# Sheet1.net
KiCad netlist of a schematic drawn in Altium Designer
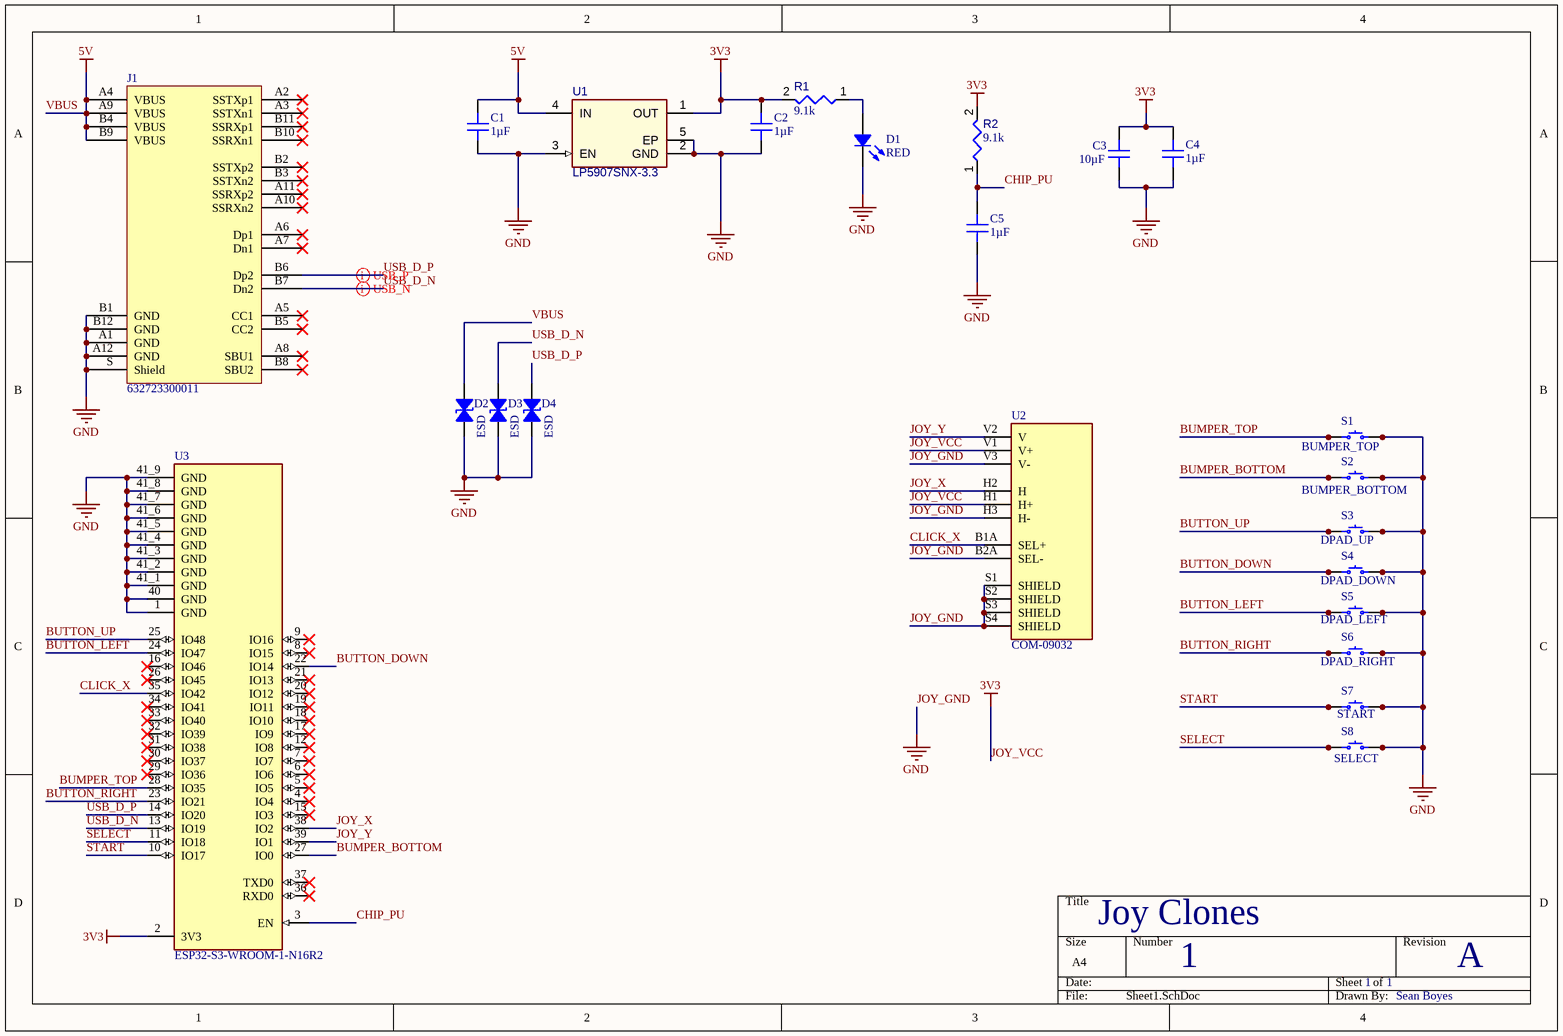
[diagram p0: Sheet1.SchDoc]

(export (version "E")
  (design (tool "Eeschema 10.0.6"))
  (components
    (comp (ref "C1")
      (value "1µF")
      (footprint "CAP 0402_1005")
      (description "CAP CER 1UF 10V X7S 0402")
      (fields (field (name "PART NUMBER") "CL05Y105KP6VPNC") (field (name "TOLERANCE") "10%"))
      (libsource (lib "Simon Fraser University") (part "CAPACITOR"))
    )
    (comp (ref "C2")
      (value "1µF")
      (footprint "CAP 0402_1005")
      (description "CAP CER 1UF 10V X7S 0402")
      (fields (field (name "PART NUMBER") "CL05Y105KP6VPNC") (field (name "TOLERANCE") "10%"))
      (libsource (lib "Simon Fraser University") (part "CAPACITOR"))
    )
    (comp (ref "C3")
      (value "10µF")
      (footprint "CAP 0603_1608")
      (description "CAP CER 10UF 6.3V X6S 0603")
      (fields (field (name "TOLERANCE") "20%") (field (name "PART NUMBER") "GRM188C80J106MEA6J"))
      (libsource (lib "Simon Fraser University") (part "CAPACITOR"))
    )
    (comp (ref "C4")
      (value "1µF")
      (footprint "CAP 0402_1005")
      (description "CAP CER 1UF 10V X7S 0402")
      (fields (field (name "PART NUMBER") "CL05Y105KP6VPNC") (field (name "TOLERANCE") "10%"))
      (libsource (lib "Simon Fraser University") (part "CAPACITOR"))
    )
    (comp (ref "C5")
      (value "1µF")
      (footprint "CAP 0402_1005")
      (description "CAP CER 1UF 10V X7S 0402")
      (fields (field (name "PART NUMBER") "CL05Y105KP6VPNC") (field (name "TOLERANCE") "10%"))
      (libsource (lib "Simon Fraser University") (part "CAPACITOR"))
    )
    (comp (ref "D1")
      (value "RED")
      (footprint "LED 0603_1608 RED")
      (description "LED RED CLEAR 2SMD")
      (fields
        (field (name "MANUFACTURER") "Everlight Electronics Co Ltd")
        (field (name "PART NUMBER") "EAST16084RA0")
      )
      (libsource (lib "Simon Fraser University") (part "LED"))
    )
    (comp (ref "D2")
      (value "ESD")
      (footprint "0402")
      (description "TVS DIODE 5V 8.2V 2X2DFN")
      (fields (field (name "PART NUMBER") "ESDM3051N2T5G") (field (name "MANUFACTURER") "ON Semiconductor"))
      (libsource (lib "Simon Fraser University") (part "DIODE TVS"))
    )
    (comp (ref "D3")
      (value "ESD")
      (footprint "0402")
      (description "TVS DIODE 5V 8.2V 2X2DFN")
      (fields (field (name "PART NUMBER") "ESDM3051N2T5G") (field (name "MANUFACTURER") "ON Semiconductor"))
      (libsource (lib "Simon Fraser University") (part "DIODE TVS"))
    )
    (comp (ref "D4")
      (value "ESD")
      (footprint "0402")
      (description "TVS DIODE 5V 8.2V 2X2DFN")
      (fields (field (name "PART NUMBER") "ESDM3051N2T5G") (field (name "MANUFACTURER") "ON Semiconductor"))
      (libsource (lib "Simon Fraser University") (part "DIODE TVS"))
    )
    (comp (ref "J1")
      (value "632723300011")
      (footprint "WURTH 632723300011")
      (description "CONN RCP USB3.1 TYPEC 24P SMD RA")
      (fields (field (name "MANUFACTURER") "Würth Elektronik"))
      (libsource (lib "Simon Fraser University") (part "USB 3.0 TYPE C"))
    )
    (comp (ref "R1")
      (value "9.1k")
      (footprint "RESC0402(1005)_L")
      (description "9K1 0.063W 5% 0402 (1005 Metric)  SMD")
      (fields (field (name "POWER") "63mW") (field (name "TOLERANCE") "5%"))
      (libsource (lib "Simon Fraser University") (part "Res"))
    )
    (comp (ref "R2")
      (value "9.1k")
      (footprint "RESC0402(1005)_L")
      (description "9K1 0.063W 5% 0402 (1005 Metric)  SMD")
      (fields (field (name "POWER") "63mW") (field (name "TOLERANCE") "5%"))
      (libsource (lib "Simon Fraser University") (part "Res"))
    )
    (comp (ref "S1")
      (value "BUMPER_TOP")
      (footprint "C&K PTS810")
      (description "SWITCH TACTILE SPST-NO 0.05A 16V")
      (fields (field (name "PART NUMBER") "PTS810 SJM 250 SMTR LFS") (field (name "MANUFACTURER") "C&K"))
      (libsource (lib "Simon Fraser University") (part "SPST-NO 4 PIN"))
    )
    (comp (ref "S2")
      (value "BUMPER_BOTTOM")
      (footprint "C&K PTS810")
      (description "SWITCH TACTILE SPST-NO 0.05A 16V")
      (fields (field (name "PART NUMBER") "PTS810 SJM 250 SMTR LFS") (field (name "MANUFACTURER") "C&K"))
      (libsource (lib "Simon Fraser University") (part "SPST-NO 4 PIN"))
    )
    (comp (ref "S3")
      (value "DPAD_UP")
      (footprint "C&K PTS810")
      (description "SWITCH TACTILE SPST-NO 0.05A 16V")
      (fields (field (name "PART NUMBER") "PTS810 SJM 250 SMTR LFS") (field (name "MANUFACTURER") "C&K"))
      (libsource (lib "Simon Fraser University") (part "SPST-NO 4 PIN"))
    )
    (comp (ref "S4")
      (value "DPAD_DOWN")
      (footprint "C&K PTS810")
      (description "SWITCH TACTILE SPST-NO 0.05A 16V")
      (fields (field (name "PART NUMBER") "PTS810 SJM 250 SMTR LFS") (field (name "MANUFACTURER") "C&K"))
      (libsource (lib "Simon Fraser University") (part "SPST-NO 4 PIN"))
    )
    (comp (ref "S5")
      (value "DPAD_LEFT")
      (footprint "C&K PTS810")
      (description "SWITCH TACTILE SPST-NO 0.05A 16V")
      (fields (field (name "PART NUMBER") "PTS810 SJM 250 SMTR LFS") (field (name "MANUFACTURER") "C&K"))
      (libsource (lib "Simon Fraser University") (part "SPST-NO 4 PIN"))
    )
    (comp (ref "S6")
      (value "DPAD_RIGHT")
      (footprint "C&K PTS810")
      (description "SWITCH TACTILE SPST-NO 0.05A 16V")
      (fields (field (name "PART NUMBER") "PTS810 SJM 250 SMTR LFS") (field (name "MANUFACTURER") "C&K"))
      (libsource (lib "Simon Fraser University") (part "SPST-NO 4 PIN"))
    )
    (comp (ref "S7")
      (value "START")
      (footprint "C&K PTS810")
      (description "SWITCH TACTILE SPST-NO 0.05A 16V")
      (fields (field (name "PART NUMBER") "PTS810 SJM 250 SMTR LFS") (field (name "MANUFACTURER") "C&K"))
      (libsource (lib "Simon Fraser University") (part "SPST-NO 4 PIN"))
    )
    (comp (ref "S8")
      (value "SELECT")
      (footprint "C&K PTS810")
      (description "SWITCH TACTILE SPST-NO 0.05A 16V")
      (fields (field (name "PART NUMBER") "PTS810 SJM 250 SMTR LFS") (field (name "MANUFACTURER") "C&K"))
      (libsource (lib "Simon Fraser University") (part "SPST-NO 4 PIN"))
    )
    (comp (ref "U1")
      (value "LP5907SNX-3.3")
      (footprint "TI-DQN4-480X480TP_V")
      (description "Ultra-Low-Noise, Low-IQ LDO, 3.3 V, 0.25 A, -40 to 125 degC, 4-Pin X2SON, RoHS, Tape and Reel")
      (libsource (lib "Simon Fraser University") (part "CMP-00094-7"))
    )
    (comp (ref "U2")
      (value "COM-09032")
      (footprint "XDCR_COM-09032")
      (description "Thumb Joystick")
      (libsource (lib "COM-09032") (part "COM-09032"))
    )
    (comp (ref "U3")
      (value "ESP32-S3-WROOM-1-N16R2")
      (footprint "XCVR_ESP32-S3-WROOM-1-N16R2")
      (description "Bluetooth, WiFi 802.11b/g/n, Bluetooth v5.0 Transceiver Module 2.4GHz PCB Trace Surface Mount")
      (fields (field (name "MF") "Espressif Systems"))
      (libsource (lib "Simon Fraser University") (part "ESP32-S3-WROOM-1-N16R2"))
    )
  )
  (nets
    (net (code "1") (name "/BUMPER_BOTTOM") (class "Default")
      (node (ref "S2") (pin "1") (pinfunction "1_1") (pintype "passive"))
      (node (ref "S2") (pin "2") (pinfunction "2_2") (pintype "passive"))
      (node (ref "U3") (pin "27") (pinfunction "IO0_27") (pintype "bidirectional"))
    )
    (net (code "2") (name "/BUMPER_TOP") (class "Default")
      (node (ref "S1") (pin "1") (pinfunction "1_1") (pintype "passive"))
      (node (ref "S1") (pin "2") (pinfunction "2_2") (pintype "passive"))
      (node (ref "U3") (pin "28") (pinfunction "IO35_28") (pintype "bidirectional"))
    )
    (net (code "3") (name "/BUTTON_DOWN") (class "Default")
      (node (ref "S4") (pin "1") (pinfunction "1_1") (pintype "passive"))
      (node (ref "S4") (pin "2") (pinfunction "2_2") (pintype "passive"))
      (node (ref "U3") (pin "22") (pinfunction "IO14_22") (pintype "bidirectional"))
    )
    (net (code "4") (name "/BUTTON_LEFT") (class "Default")
      (node (ref "S5") (pin "1") (pinfunction "1_1") (pintype "passive"))
      (node (ref "S5") (pin "2") (pinfunction "2_2") (pintype "passive"))
      (node (ref "U3") (pin "24") (pinfunction "IO47_24") (pintype "bidirectional"))
    )
    (net (code "5") (name "/BUTTON_RIGHT") (class "Default")
      (node (ref "S6") (pin "1") (pinfunction "1_1") (pintype "passive"))
      (node (ref "S6") (pin "2") (pinfunction "2_2") (pintype "passive"))
      (node (ref "U3") (pin "23") (pinfunction "IO21_23") (pintype "bidirectional"))
    )
    (net (code "6") (name "/BUTTON_UP") (class "Default")
      (node (ref "S3") (pin "1") (pinfunction "1_1") (pintype "passive"))
      (node (ref "S3") (pin "2") (pinfunction "2_2") (pintype "passive"))
      (node (ref "U3") (pin "25") (pinfunction "IO48_25") (pintype "bidirectional"))
    )
    (net (code "7") (name "/CHIP_PU") (class "Default")
      (node (ref "C5") (pin "2") (pinfunction "2_2") (pintype "passive"))
      (node (ref "R2") (pin "1") (pinfunction "1_1") (pintype "passive"))
      (node (ref "U3") (pin "3") (pinfunction "EN_3") (pintype "input"))
    )
    (net (code "8") (name "/CLICK_X") (class "Default")
      (node (ref "U2") (pin "B1A") (pinfunction "SEL+_B1A") (pintype "passive"))
      (node (ref "U3") (pin "35") (pinfunction "IO42_35") (pintype "bidirectional"))
    )
    (net (code "9") (name "/JOY_X") (class "Default")
      (node (ref "U2") (pin "H2") (pinfunction "H_H2") (pintype "passive"))
      (node (ref "U3") (pin "38") (pinfunction "IO2_38") (pintype "bidirectional"))
    )
    (net (code "10") (name "/JOY_Y") (class "Default")
      (node (ref "U2") (pin "V2") (pinfunction "V_V2") (pintype "passive"))
      (node (ref "U3") (pin "39") (pinfunction "IO1_39") (pintype "bidirectional"))
    )
    (net (code "11") (name "/SELECT") (class "Default")
      (node (ref "S8") (pin "1") (pinfunction "1_1") (pintype "passive"))
      (node (ref "S8") (pin "2") (pinfunction "2_2") (pintype "passive"))
      (node (ref "U3") (pin "11") (pinfunction "IO18_11") (pintype "bidirectional"))
    )
    (net (code "12") (name "/START") (class "Default")
      (node (ref "S7") (pin "1") (pinfunction "1_1") (pintype "passive"))
      (node (ref "S7") (pin "2") (pinfunction "2_2") (pintype "passive"))
      (node (ref "U3") (pin "10") (pinfunction "IO17_10") (pintype "bidirectional"))
    )
    (net (code "13") (name "/USB_D_N") (class "Default")
      (node (ref "D3") (pin "1") (pinfunction "1_1") (pintype "passive"))
      (node (ref "J1") (pin "B7") (pinfunction "Dn2_B7") (pintype "passive"))
      (node (ref "U3") (pin "13") (pinfunction "IO19_13") (pintype "bidirectional"))
    )
    (net (code "14") (name "/USB_D_P") (class "Default")
      (node (ref "D4") (pin "1") (pinfunction "1_1") (pintype "passive"))
      (node (ref "J1") (pin "B6") (pinfunction "Dp2_B6") (pintype "passive"))
      (node (ref "U3") (pin "14") (pinfunction "IO20_14") (pintype "bidirectional"))
    )
    (net (code "15") (name "3V3") (class "Default")
      (node (ref "C2") (pin "2") (pinfunction "2_2") (pintype "passive"))
      (node (ref "C3") (pin "2") (pinfunction "2_2") (pintype "passive"))
      (node (ref "C4") (pin "2") (pinfunction "2_2") (pintype "passive"))
      (node (ref "R1") (pin "2") (pinfunction "2_2") (pintype "passive"))
      (node (ref "R2") (pin "2") (pinfunction "2_2") (pintype "passive"))
      (node (ref "U1") (pin "1") (pinfunction "OUT_1") (pintype "power_in"))
      (node (ref "U2") (pin "H1") (pinfunction "H+_H1") (pintype "passive"))
      (node (ref "U2") (pin "V1") (pinfunction "V+_V1") (pintype "passive"))
      (node (ref "U3") (pin "2") (pinfunction "3V3_2") (pintype "power_in"))
    )
    (net (code "16") (name "5V") (class "Default")
      (node (ref "C1") (pin "2") (pinfunction "2_2") (pintype "passive"))
      (node (ref "D2") (pin "1") (pinfunction "1_1") (pintype "passive"))
      (node (ref "J1") (pin "A4") (pinfunction "VBUS_A4") (pintype "passive"))
      (node (ref "J1") (pin "A9") (pinfunction "VBUS_A9") (pintype "passive"))
      (node (ref "J1") (pin "B4") (pinfunction "VBUS_B4") (pintype "passive"))
      (node (ref "J1") (pin "B9") (pinfunction "VBUS_B9") (pintype "passive"))
      (node (ref "U1") (pin "4") (pinfunction "IN_4") (pintype "power_in"))
    )
    (net (code "17") (name "GND") (class "Default")
      (node (ref "C1") (pin "1") (pinfunction "1_1") (pintype "passive"))
      (node (ref "C2") (pin "1") (pinfunction "1_1") (pintype "passive"))
      (node (ref "C3") (pin "1") (pinfunction "1_1") (pintype "passive"))
      (node (ref "C4") (pin "1") (pinfunction "1_1") (pintype "passive"))
      (node (ref "C5") (pin "1") (pinfunction "1_1") (pintype "passive"))
      (node (ref "D1") (pin "2") (pinfunction "2_2") (pintype "passive"))
      (node (ref "D2") (pin "2") (pinfunction "2_2") (pintype "passive"))
      (node (ref "D3") (pin "2") (pinfunction "2_2") (pintype "passive"))
      (node (ref "D4") (pin "2") (pinfunction "2_2") (pintype "passive"))
      (node (ref "J1") (pin "A1") (pinfunction "GND_A1") (pintype "passive"))
      (node (ref "J1") (pin "A12") (pinfunction "GND_A12") (pintype "passive"))
      (node (ref "J1") (pin "B1") (pinfunction "GND_B1") (pintype "passive"))
      (node (ref "J1") (pin "B12") (pinfunction "GND_B12") (pintype "passive"))
      (node (ref "J1") (pin "S") (pinfunction "Shield_S") (pintype "passive"))
      (node (ref "S1") (pin "3") (pinfunction "3_3") (pintype "passive"))
      (node (ref "S1") (pin "4") (pinfunction "4_4") (pintype "passive"))
      (node (ref "S2") (pin "3") (pinfunction "3_3") (pintype "passive"))
      (node (ref "S2") (pin "4") (pinfunction "4_4") (pintype "passive"))
      (node (ref "S3") (pin "3") (pinfunction "3_3") (pintype "passive"))
      (node (ref "S3") (pin "4") (pinfunction "4_4") (pintype "passive"))
      (node (ref "S4") (pin "3") (pinfunction "3_3") (pintype "passive"))
      (node (ref "S4") (pin "4") (pinfunction "4_4") (pintype "passive"))
      (node (ref "S5") (pin "3") (pinfunction "3_3") (pintype "passive"))
      (node (ref "S5") (pin "4") (pinfunction "4_4") (pintype "passive"))
      (node (ref "S6") (pin "3") (pinfunction "3_3") (pintype "passive"))
      (node (ref "S6") (pin "4") (pinfunction "4_4") (pintype "passive"))
      (node (ref "S7") (pin "3") (pinfunction "3_3") (pintype "passive"))
      (node (ref "S7") (pin "4") (pinfunction "4_4") (pintype "passive"))
      (node (ref "S8") (pin "3") (pinfunction "3_3") (pintype "passive"))
      (node (ref "S8") (pin "4") (pinfunction "4_4") (pintype "passive"))
      (node (ref "U1") (pin "2") (pinfunction "GND_2") (pintype "power_in"))
      (node (ref "U1") (pin "3") (pinfunction "EN_3") (pintype "input"))
      (node (ref "U1") (pin "5") (pinfunction "EP_5") (pintype "power_in"))
      (node (ref "U2") (pin "B2A") (pinfunction "SEL-_B2A") (pintype "passive"))
      (node (ref "U2") (pin "H3") (pinfunction "H-_H3") (pintype "passive"))
      (node (ref "U2") (pin "S1") (pinfunction "SHIELD_S1") (pintype "passive"))
      (node (ref "U2") (pin "S2") (pinfunction "SHIELD_S2") (pintype "passive"))
      (node (ref "U2") (pin "S3") (pinfunction "SHIELD_S3") (pintype "passive"))
      (node (ref "U2") (pin "S4") (pinfunction "SHIELD_S4") (pintype "passive"))
      (node (ref "U2") (pin "V3") (pinfunction "V-_V3") (pintype "passive"))
      (node (ref "U3") (pin "1") (pinfunction "GND_1") (pintype "power_in"))
      (node (ref "U3") (pin "40") (pinfunction "GND_40") (pintype "power_in"))
      (node (ref "U3") (pin "41_1") (pinfunction "GND_41_1") (pintype "power_in"))
      (node (ref "U3") (pin "41_2") (pinfunction "GND_41_2") (pintype "power_in"))
      (node (ref "U3") (pin "41_3") (pinfunction "GND_41_3") (pintype "power_in"))
      (node (ref "U3") (pin "41_4") (pinfunction "GND_41_4") (pintype "power_in"))
      (node (ref "U3") (pin "41_5") (pinfunction "GND_41_5") (pintype "power_in"))
      (node (ref "U3") (pin "41_6") (pinfunction "GND_41_6") (pintype "power_in"))
      (node (ref "U3") (pin "41_7") (pinfunction "GND_41_7") (pintype "power_in"))
      (node (ref "U3") (pin "41_8") (pinfunction "GND_41_8") (pintype "power_in"))
      (node (ref "U3") (pin "41_9") (pinfunction "GND_41_9") (pintype "power_in"))
    )
    (net (code "18") (name "Net-(D1-Pad1)") (class "Default")
      (node (ref "D1") (pin "1") (pinfunction "1_1") (pintype "passive"))
      (node (ref "R1") (pin "1") (pinfunction "1_1") (pintype "passive"))
    )
    (net (code "19") (name "unconnected-(J1-CC1-PadA5)") (class "Default")
      (node (ref "J1") (pin "A5") (pinfunction "CC1_A5") (pintype "passive+no_connect"))
    )
    (net (code "20") (name "unconnected-(J1-CC2-PadB5)") (class "Default")
      (node (ref "J1") (pin "B5") (pinfunction "CC2_B5") (pintype "passive+no_connect"))
    )
    (net (code "21") (name "unconnected-(J1-Dn1-PadA7)") (class "Default")
      (node (ref "J1") (pin "A7") (pinfunction "Dn1_A7") (pintype "passive+no_connect"))
    )
    (net (code "22") (name "unconnected-(J1-Dp1-PadA6)") (class "Default")
      (node (ref "J1") (pin "A6") (pinfunction "Dp1_A6") (pintype "passive+no_connect"))
    )
    (net (code "23") (name "unconnected-(J1-SBU1-PadA8)") (class "Default")
      (node (ref "J1") (pin "A8") (pinfunction "SBU1_A8") (pintype "passive+no_connect"))
    )
    (net (code "24") (name "unconnected-(J1-SBU2-PadB8)") (class "Default")
      (node (ref "J1") (pin "B8") (pinfunction "SBU2_B8") (pintype "passive+no_connect"))
    )
    (net (code "25") (name "unconnected-(J1-SSRXn1-PadB10)") (class "Default")
      (node (ref "J1") (pin "B10") (pinfunction "SSRXn1_B10") (pintype "passive+no_connect"))
    )
    (net (code "26") (name "unconnected-(J1-SSRXn2-PadA10)") (class "Default")
      (node (ref "J1") (pin "A10") (pinfunction "SSRXn2_A10") (pintype "passive+no_connect"))
    )
    (net (code "27") (name "unconnected-(J1-SSRXp1-PadB11)") (class "Default")
      (node (ref "J1") (pin "B11") (pinfunction "SSRXp1_B11") (pintype "passive+no_connect"))
    )
    (net (code "28") (name "unconnected-(J1-SSRXp2-PadA11)") (class "Default")
      (node (ref "J1") (pin "A11") (pinfunction "SSRXp2_A11") (pintype "passive+no_connect"))
    )
    (net (code "29") (name "unconnected-(J1-SSTXn1-PadA3)") (class "Default")
      (node (ref "J1") (pin "A3") (pinfunction "SSTXn1_A3") (pintype "passive+no_connect"))
    )
    (net (code "30") (name "unconnected-(J1-SSTXn2-PadB3)") (class "Default")
      (node (ref "J1") (pin "B3") (pinfunction "SSTXn2_B3") (pintype "passive+no_connect"))
    )
    (net (code "31") (name "unconnected-(J1-SSTXp1-PadA2)") (class "Default")
      (node (ref "J1") (pin "A2") (pinfunction "SSTXp1_A2") (pintype "passive+no_connect"))
    )
    (net (code "32") (name "unconnected-(J1-SSTXp2-PadB2)") (class "Default")
      (node (ref "J1") (pin "B2") (pinfunction "SSTXp2_B2") (pintype "passive+no_connect"))
    )
    (net (code "33") (name "unconnected-(U3-IO3-Pad15)") (class "Default")
      (node (ref "U3") (pin "15") (pinfunction "IO3_15") (pintype "bidirectional+no_connect"))
    )
    (net (code "34") (name "unconnected-(U3-IO4-Pad4)") (class "Default")
      (node (ref "U3") (pin "4") (pinfunction "IO4_4") (pintype "bidirectional+no_connect"))
    )
    (net (code "35") (name "unconnected-(U3-IO5-Pad5)") (class "Default")
      (node (ref "U3") (pin "5") (pinfunction "IO5_5") (pintype "bidirectional+no_connect"))
    )
    (net (code "36") (name "unconnected-(U3-IO6-Pad6)") (class "Default")
      (node (ref "U3") (pin "6") (pinfunction "IO6_6") (pintype "bidirectional+no_connect"))
    )
    (net (code "37") (name "unconnected-(U3-IO7-Pad7)") (class "Default")
      (node (ref "U3") (pin "7") (pinfunction "IO7_7") (pintype "bidirectional+no_connect"))
    )
    (net (code "38") (name "unconnected-(U3-IO8-Pad12)") (class "Default")
      (node (ref "U3") (pin "12") (pinfunction "IO8_12") (pintype "bidirectional+no_connect"))
    )
    (net (code "39") (name "unconnected-(U3-IO9-Pad17)") (class "Default")
      (node (ref "U3") (pin "17") (pinfunction "IO9_17") (pintype "bidirectional+no_connect"))
    )
    (net (code "40") (name "unconnected-(U3-IO10-Pad18)") (class "Default")
      (node (ref "U3") (pin "18") (pinfunction "IO10_18") (pintype "bidirectional+no_connect"))
    )
    (net (code "41") (name "unconnected-(U3-IO11-Pad19)") (class "Default")
      (node (ref "U3") (pin "19") (pinfunction "IO11_19") (pintype "bidirectional+no_connect"))
    )
    (net (code "42") (name "unconnected-(U3-IO12-Pad20)") (class "Default")
      (node (ref "U3") (pin "20") (pinfunction "IO12_20") (pintype "bidirectional+no_connect"))
    )
    (net (code "43") (name "unconnected-(U3-IO13-Pad21)") (class "Default")
      (node (ref "U3") (pin "21") (pinfunction "IO13_21") (pintype "bidirectional+no_connect"))
    )
    (net (code "44") (name "unconnected-(U3-IO15-Pad8)") (class "Default")
      (node (ref "U3") (pin "8") (pinfunction "IO15_8") (pintype "bidirectional+no_connect"))
    )
    (net (code "45") (name "unconnected-(U3-IO16-Pad9)") (class "Default")
      (node (ref "U3") (pin "9") (pinfunction "IO16_9") (pintype "bidirectional+no_connect"))
    )
    (net (code "46") (name "unconnected-(U3-IO36-Pad29)") (class "Default")
      (node (ref "U3") (pin "29") (pinfunction "IO36_29") (pintype "bidirectional+no_connect"))
    )
    (net (code "47") (name "unconnected-(U3-IO37-Pad30)") (class "Default")
      (node (ref "U3") (pin "30") (pinfunction "IO37_30") (pintype "bidirectional+no_connect"))
    )
    (net (code "48") (name "unconnected-(U3-IO38-Pad31)") (class "Default")
      (node (ref "U3") (pin "31") (pinfunction "IO38_31") (pintype "bidirectional+no_connect"))
    )
    (net (code "49") (name "unconnected-(U3-IO39-Pad32)") (class "Default")
      (node (ref "U3") (pin "32") (pinfunction "IO39_32") (pintype "bidirectional+no_connect"))
    )
    (net (code "50") (name "unconnected-(U3-IO40-Pad33)") (class "Default")
      (node (ref "U3") (pin "33") (pinfunction "IO40_33") (pintype "bidirectional+no_connect"))
    )
    (net (code "51") (name "unconnected-(U3-IO41-Pad34)") (class "Default")
      (node (ref "U3") (pin "34") (pinfunction "IO41_34") (pintype "bidirectional+no_connect"))
    )
    (net (code "52") (name "unconnected-(U3-IO45-Pad26)") (class "Default")
      (node (ref "U3") (pin "26") (pinfunction "IO45_26") (pintype "bidirectional+no_connect"))
    )
    (net (code "53") (name "unconnected-(U3-IO46-Pad16)") (class "Default")
      (node (ref "U3") (pin "16") (pinfunction "IO46_16") (pintype "bidirectional+no_connect"))
    )
    (net (code "54") (name "unconnected-(U3-RXD0-Pad36)") (class "Default")
      (node (ref "U3") (pin "36") (pinfunction "RXD0_36") (pintype "bidirectional+no_connect"))
    )
    (net (code "55") (name "unconnected-(U3-TXD0-Pad37)") (class "Default")
      (node (ref "U3") (pin "37") (pinfunction "TXD0_37") (pintype "bidirectional+no_connect"))
    )
  )
)
